# HW_ITC_LE.net
KiCad netlist of a schematic drawn in Altium Designer
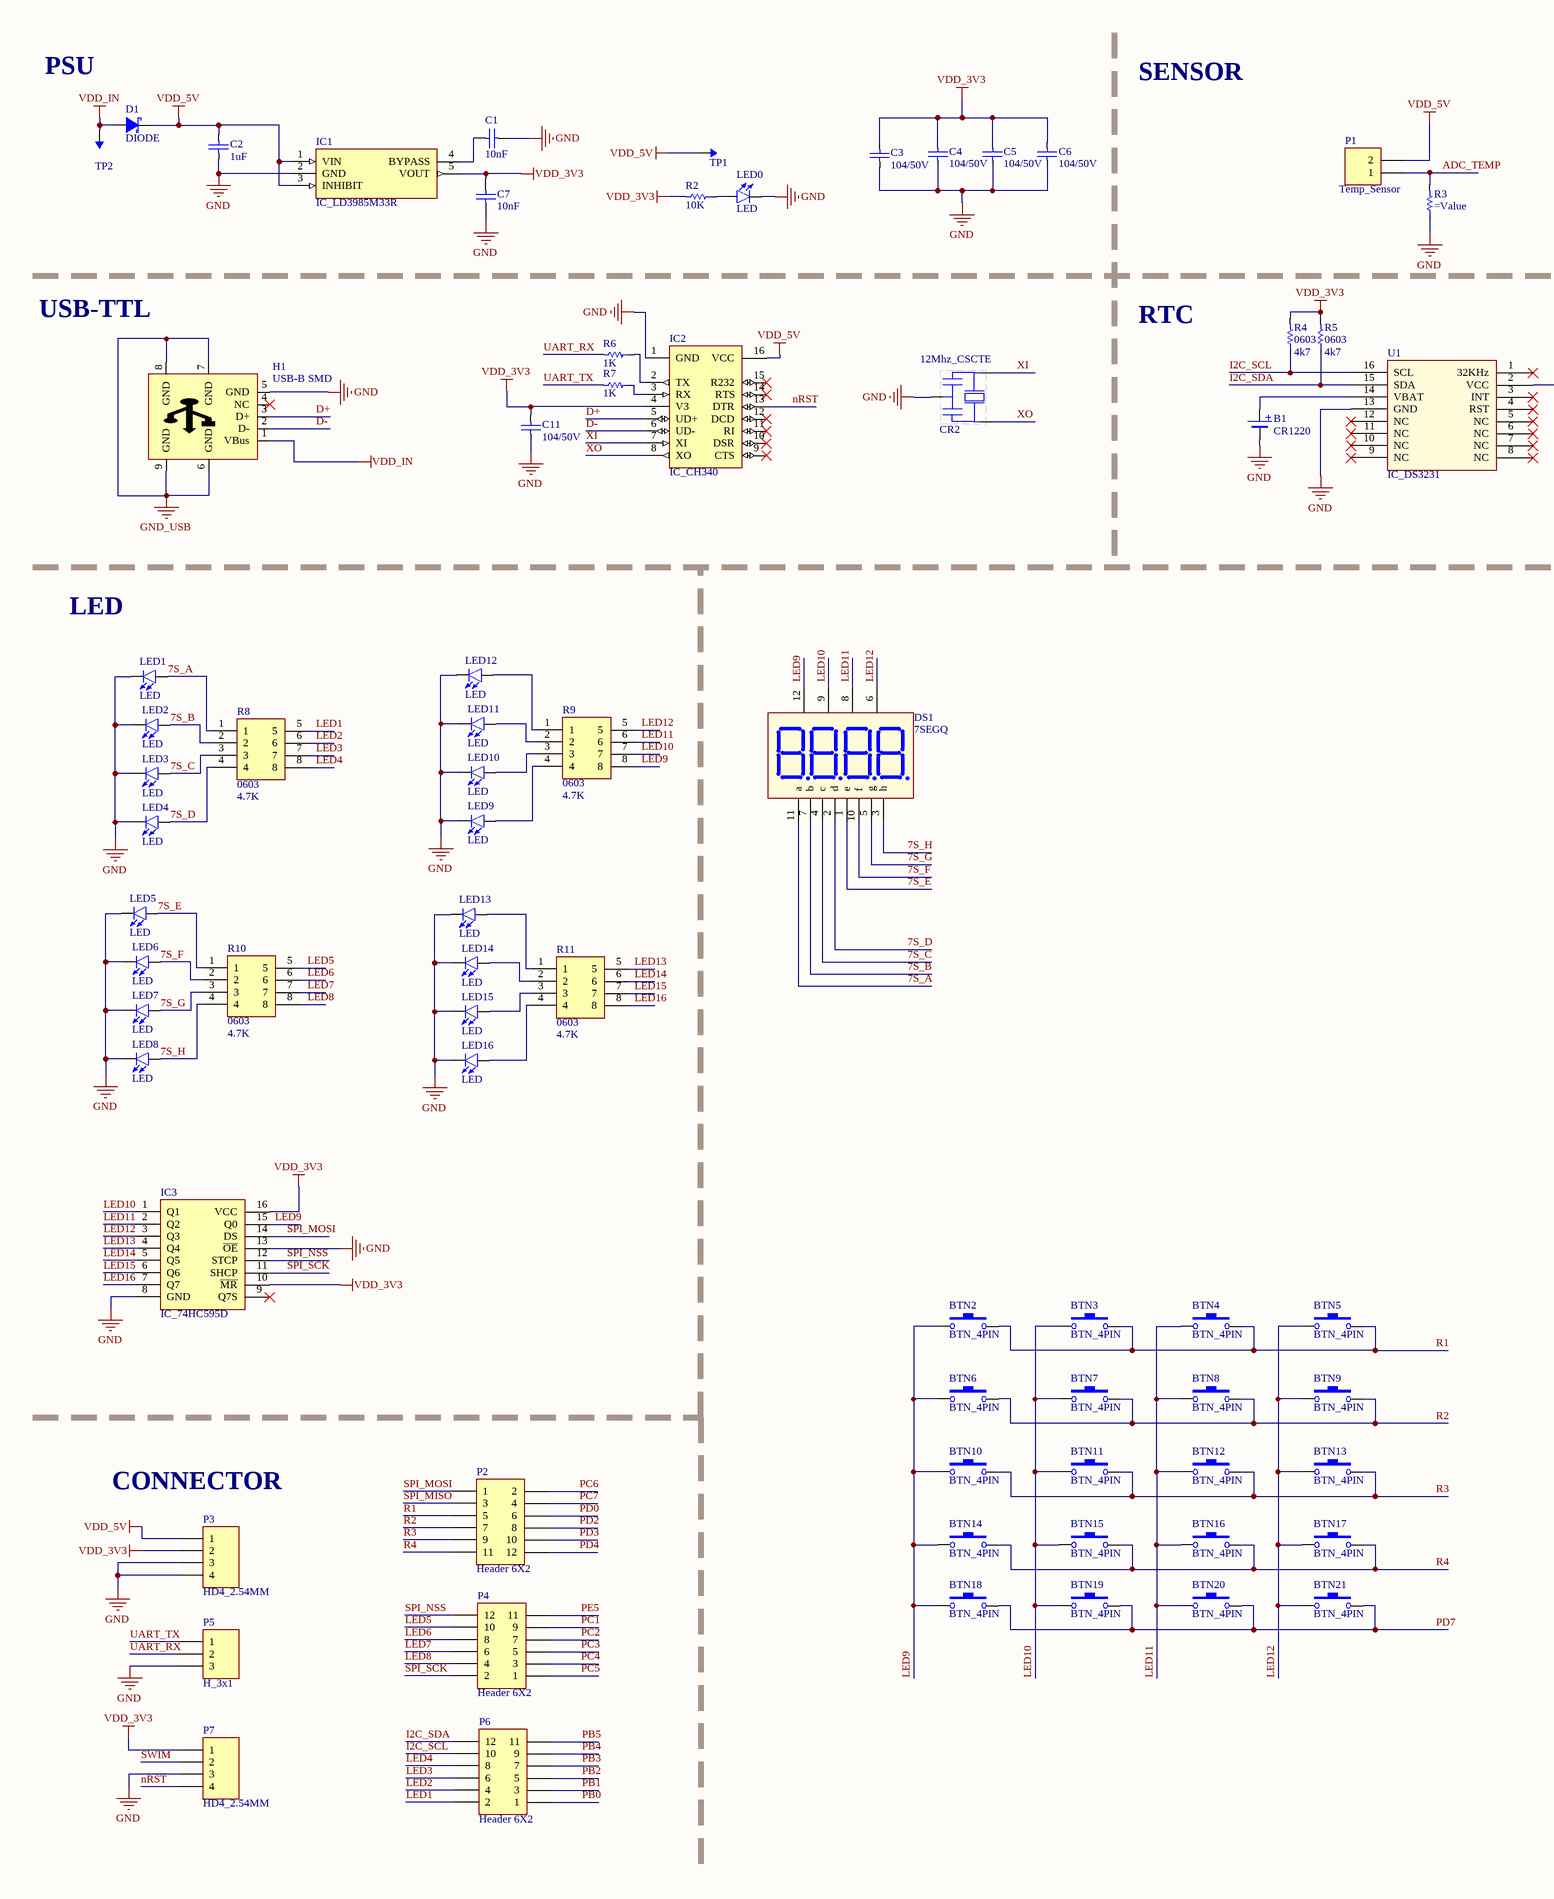
[diagram p0: HW_ITC_LE.SchDoc, left]
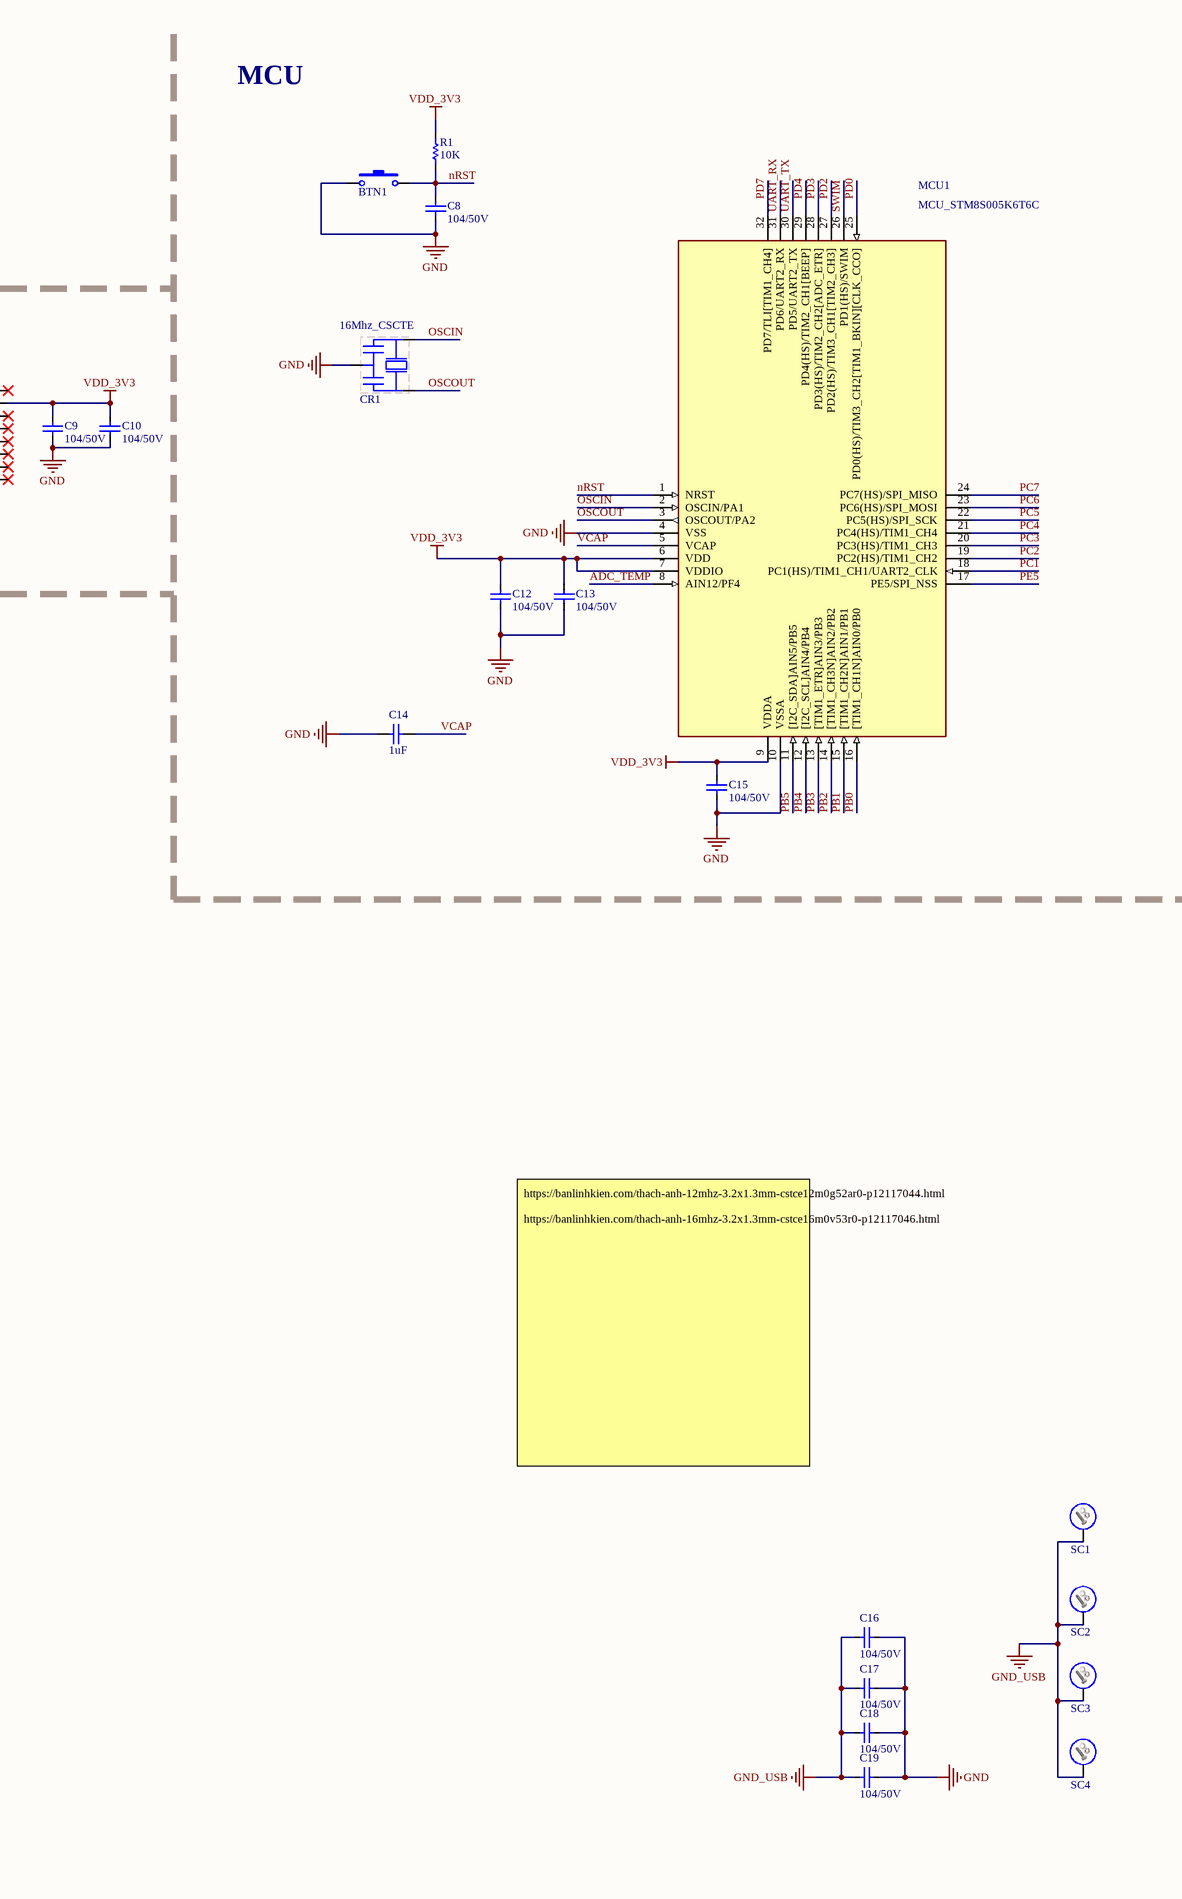
[diagram p1: HW_ITC_LE.SchDoc, right]

(export (version "E")
  (design (tool "Eeschema 10.0.6"))
  (components
    (comp (ref "B1")
      (value "CR1220")
      (footprint "CR1220")
      (libsource (lib "ITC_HHC") (part "Battery_CR1220"))
    )
    (comp (ref "BTN1")
      (value "EVQ-21307K")
      (footprint "BUTTON_2P_SMD")
      (description "PANASONIC   EVQ-21307K   SWITCH, TACTILE, SPST-NO, 20mA, 15VDC")
      (fields (field (name "MANUFACTURER") "Panasonic"))
      (libsource (lib "ITC_HHC") (part "BTN_2P_SMD"))
    )
    (comp (ref "BTN2")
      (value "BTN_4PIN")
      (footprint "BTN_4PIN - 6X6mm")
      (fields (field (name "PUBLISHER") "Altium Limited"))
      (libsource (lib "ITC_HHC") (part "BTN_4PIN"))
    )
    (comp (ref "BTN3")
      (value "BTN_4PIN")
      (footprint "BTN_4PIN - 6X6mm")
      (fields (field (name "PUBLISHER") "Altium Limited"))
      (libsource (lib "ITC_HHC") (part "BTN_4PIN"))
    )
    (comp (ref "BTN4")
      (value "BTN_4PIN")
      (footprint "BTN_4PIN - 6X6mm")
      (fields (field (name "PUBLISHER") "Altium Limited"))
      (libsource (lib "ITC_HHC") (part "BTN_4PIN"))
    )
    (comp (ref "BTN5")
      (value "BTN_4PIN")
      (footprint "BTN_4PIN - 6X6mm")
      (fields (field (name "PUBLISHER") "Altium Limited"))
      (libsource (lib "ITC_HHC") (part "BTN_4PIN"))
    )
    (comp (ref "BTN6")
      (value "BTN_4PIN")
      (footprint "BTN_4PIN - 6X6mm")
      (fields (field (name "PUBLISHER") "Altium Limited"))
      (libsource (lib "ITC_HHC") (part "BTN_4PIN"))
    )
    (comp (ref "BTN7")
      (value "BTN_4PIN")
      (footprint "BTN_4PIN - 6X6mm")
      (fields (field (name "PUBLISHER") "Altium Limited"))
      (libsource (lib "ITC_HHC") (part "BTN_4PIN"))
    )
    (comp (ref "BTN8")
      (value "BTN_4PIN")
      (footprint "BTN_4PIN - 6X6mm")
      (fields (field (name "PUBLISHER") "Altium Limited"))
      (libsource (lib "ITC_HHC") (part "BTN_4PIN"))
    )
    (comp (ref "BTN9")
      (value "BTN_4PIN")
      (footprint "BTN_4PIN - 6X6mm")
      (fields (field (name "PUBLISHER") "Altium Limited"))
      (libsource (lib "ITC_HHC") (part "BTN_4PIN"))
    )
    (comp (ref "BTN10")
      (value "BTN_4PIN")
      (footprint "BTN_4PIN - 6X6mm")
      (fields (field (name "PUBLISHER") "Altium Limited"))
      (libsource (lib "ITC_HHC") (part "BTN_4PIN"))
    )
    (comp (ref "BTN11")
      (value "BTN_4PIN")
      (footprint "BTN_4PIN - 6X6mm")
      (fields (field (name "PUBLISHER") "Altium Limited"))
      (libsource (lib "ITC_HHC") (part "BTN_4PIN"))
    )
    (comp (ref "BTN12")
      (value "BTN_4PIN")
      (footprint "BTN_4PIN - 6X6mm")
      (fields (field (name "PUBLISHER") "Altium Limited"))
      (libsource (lib "ITC_HHC") (part "BTN_4PIN"))
    )
    (comp (ref "BTN13")
      (value "BTN_4PIN")
      (footprint "BTN_4PIN - 6X6mm")
      (fields (field (name "PUBLISHER") "Altium Limited"))
      (libsource (lib "ITC_HHC") (part "BTN_4PIN"))
    )
    (comp (ref "BTN14")
      (value "BTN_4PIN")
      (footprint "BTN_4PIN - 6X6mm")
      (fields (field (name "PUBLISHER") "Altium Limited"))
      (libsource (lib "ITC_HHC") (part "BTN_4PIN"))
    )
    (comp (ref "BTN15")
      (value "BTN_4PIN")
      (footprint "BTN_4PIN - 6X6mm")
      (fields (field (name "PUBLISHER") "Altium Limited"))
      (libsource (lib "ITC_HHC") (part "BTN_4PIN"))
    )
    (comp (ref "BTN16")
      (value "BTN_4PIN")
      (footprint "BTN_4PIN - 6X6mm")
      (fields (field (name "PUBLISHER") "Altium Limited"))
      (libsource (lib "ITC_HHC") (part "BTN_4PIN"))
    )
    (comp (ref "BTN17")
      (value "BTN_4PIN")
      (footprint "BTN_4PIN - 6X6mm")
      (fields (field (name "PUBLISHER") "Altium Limited"))
      (libsource (lib "ITC_HHC") (part "BTN_4PIN"))
    )
    (comp (ref "BTN18")
      (value "BTN_4PIN")
      (footprint "BTN_4PIN - 6X6mm")
      (fields (field (name "PUBLISHER") "Altium Limited"))
      (libsource (lib "ITC_HHC") (part "BTN_4PIN"))
    )
    (comp (ref "BTN19")
      (value "BTN_4PIN")
      (footprint "BTN_4PIN - 6X6mm")
      (fields (field (name "PUBLISHER") "Altium Limited"))
      (libsource (lib "ITC_HHC") (part "BTN_4PIN"))
    )
    (comp (ref "BTN20")
      (value "BTN_4PIN")
      (footprint "BTN_4PIN - 6X6mm")
      (fields (field (name "PUBLISHER") "Altium Limited"))
      (libsource (lib "ITC_HHC") (part "BTN_4PIN"))
    )
    (comp (ref "BTN21")
      (value "BTN_4PIN")
      (footprint "BTN_4PIN - 6X6mm")
      (fields (field (name "PUBLISHER") "Altium Limited"))
      (libsource (lib "ITC_HHC") (part "BTN_4PIN"))
    )
    (comp (ref "C1")
      (value "10nF")
      (footprint "C0603")
      (description "Non-polarised capacitor")
      (libsource (lib "ITC_HHC") (part "Capacitor - non polarized"))
    )
    (comp (ref "C2")
      (value "1uF")
      (footprint "C0603")
      (description "CAP-CER-104-50V-0603-10%")
      (fields
        (field (name "MANUFACTURER") "Samsung")
        (field (name "MANUFACTURER PART NUMBER") "CL10B104KB8NNNC")
      )
      (libsource (lib "ITC_HHC") (part "C0603_104_50V"))
    )
    (comp (ref "C3")
      (value "104/50V")
      (footprint "C0603")
      (description "CAP-CER-104-50V-0603-10%")
      (fields
        (field (name "MANUFACTURER") "Samsung")
        (field (name "MANUFACTURER PART NUMBER") "CL10B104KB8NNNC")
      )
      (libsource (lib "ITC_HHC") (part "C0603_104_50V"))
    )
    (comp (ref "C4")
      (value "104/50V")
      (footprint "C0603")
      (description "CAP-CER-104-50V-0603-10%")
      (fields
        (field (name "MANUFACTURER") "Samsung")
        (field (name "MANUFACTURER PART NUMBER") "CL10B104KB8NNNC")
      )
      (libsource (lib "ITC_HHC") (part "C0603_104_50V"))
    )
    (comp (ref "C5")
      (value "104/50V")
      (footprint "C0603")
      (description "CAP-CER-104-50V-0603-10%")
      (fields
        (field (name "MANUFACTURER") "Samsung")
        (field (name "MANUFACTURER PART NUMBER") "CL10B104KB8NNNC")
      )
      (libsource (lib "ITC_HHC") (part "C0603_104_50V"))
    )
    (comp (ref "C6")
      (value "104/50V")
      (footprint "C0603")
      (description "CAP-CER-104-50V-0603-10%")
      (fields
        (field (name "MANUFACTURER") "Samsung")
        (field (name "MANUFACTURER PART NUMBER") "CL10B104KB8NNNC")
      )
      (libsource (lib "ITC_HHC") (part "C0603_104_50V"))
    )
    (comp (ref "C7")
      (value "10nF")
      (footprint "C0603")
      (description "Non-polarised capacitor")
      (libsource (lib "ITC_HHC") (part "Capacitor - non polarized"))
    )
    (comp (ref "C8")
      (value "104/50V")
      (footprint "C0603")
      (description "CAP-CER-104-50V-0603-10%")
      (fields
        (field (name "MANUFACTURER") "Samsung")
        (field (name "MANUFACTURER PART NUMBER") "CL10B104KB8NNNC")
      )
      (libsource (lib "ITC_HHC") (part "C0603_104_50V"))
    )
    (comp (ref "C9")
      (value "104/50V")
      (footprint "C0603")
      (description "CAP-CER-104-50V-0603-10%")
      (fields
        (field (name "MANUFACTURER") "Samsung")
        (field (name "MANUFACTURER PART NUMBER") "CL10B104KB8NNNC")
      )
      (libsource (lib "ITC_HHC") (part "C0603_104_50V"))
    )
    (comp (ref "C10")
      (value "104/50V")
      (footprint "C0603")
      (description "CAP-CER-104-50V-0603-10%")
      (fields
        (field (name "MANUFACTURER") "Samsung")
        (field (name "MANUFACTURER PART NUMBER") "CL10B104KB8NNNC")
      )
      (libsource (lib "ITC_HHC") (part "C0603_104_50V"))
    )
    (comp (ref "C11")
      (value "104/50V")
      (footprint "C0603")
      (description "CAP-CER-104-50V-0603-10%")
      (fields
        (field (name "MANUFACTURER") "Samsung")
        (field (name "MANUFACTURER PART NUMBER") "CL10B104KB8NNNC")
      )
      (libsource (lib "ITC_HHC") (part "C0603_104_50V"))
    )
    (comp (ref "C12")
      (value "104/50V")
      (footprint "C0603")
      (description "CAP-CER-104-50V-0603-10%")
      (fields
        (field (name "MANUFACTURER") "Samsung")
        (field (name "MANUFACTURER PART NUMBER") "CL10B104KB8NNNC")
      )
      (libsource (lib "ITC_HHC") (part "C0603_104_50V"))
    )
    (comp (ref "C13")
      (value "104/50V")
      (footprint "C0603")
      (description "CAP-CER-104-50V-0603-10%")
      (fields
        (field (name "MANUFACTURER") "Samsung")
        (field (name "MANUFACTURER PART NUMBER") "CL10B104KB8NNNC")
      )
      (libsource (lib "ITC_HHC") (part "C0603_104_50V"))
    )
    (comp (ref "C14")
      (value "1uF")
      (footprint "C0603")
      (description "Non-polarised capacitor")
      (libsource (lib "ITC_HHC") (part "Capacitor - non polarized"))
    )
    (comp (ref "C15")
      (value "104/50V")
      (footprint "C0603")
      (description "CAP-CER-104-50V-0603-10%")
      (fields
        (field (name "MANUFACTURER") "Samsung")
        (field (name "MANUFACTURER PART NUMBER") "CL10B104KB8NNNC")
      )
      (libsource (lib "ITC_HHC") (part "C0603_104_50V"))
    )
    (comp (ref "C16")
      (value "104/50V")
      (footprint "C0603")
      (description "CAP-CER-104-50V-0603-10%")
      (fields
        (field (name "MANUFACTURER") "Samsung")
        (field (name "MANUFACTURER PART NUMBER") "CL10B104KB8NNNC")
      )
      (libsource (lib "ITC_HHC") (part "C0603_104_50V"))
    )
    (comp (ref "C17")
      (value "104/50V")
      (footprint "C0603")
      (description "CAP-CER-104-50V-0603-10%")
      (fields
        (field (name "MANUFACTURER") "Samsung")
        (field (name "MANUFACTURER PART NUMBER") "CL10B104KB8NNNC")
      )
      (libsource (lib "ITC_HHC") (part "C0603_104_50V"))
    )
    (comp (ref "C18")
      (value "104/50V")
      (footprint "C0603")
      (description "CAP-CER-104-50V-0603-10%")
      (fields
        (field (name "MANUFACTURER") "Samsung")
        (field (name "MANUFACTURER PART NUMBER") "CL10B104KB8NNNC")
      )
      (libsource (lib "ITC_HHC") (part "C0603_104_50V"))
    )
    (comp (ref "C19")
      (value "104/50V")
      (footprint "C0603")
      (description "CAP-CER-104-50V-0603-10%")
      (fields
        (field (name "MANUFACTURER") "Samsung")
        (field (name "MANUFACTURER PART NUMBER") "CL10B104KB8NNNC")
      )
      (libsource (lib "ITC_HHC") (part "C0603_104_50V"))
    )
    (comp (ref "CR1")
      (value "16Mhz_CSCTE")
      (footprint "CRYSTAL_CSTCE_G_4520")
      (description "CER RES 6Mhz SMD")
      (libsource (lib "ITC_HHC") (part "CR_6Mhz_CSCTE"))
    )
    (comp (ref "CR2")
      (value "12Mhz_CSCTE")
      (footprint "CRYSTAL_CSTCE_G_4520")
      (description "CER RES 6Mhz SMD")
      (libsource (lib "ITC_HHC") (part "CR_6Mhz_CSCTE"))
    )
    (comp (ref "D1")
      (value "DIODE")
      (footprint "DIODE_SOD-123")
      (description "Schottky Diode RB060MM-60TFTR")
      (fields
        (field (name "MANUFACTURER_PART_NUMBER") "RB060MM-60TFTR")
        (field (name "MOUSER PART NUMBER") "755-RB060MM-60TFTR")
      )
      (libsource (lib "ITC_HHC") (part "DIODE_SOD-123FL"))
    )
    (comp (ref "DS1")
      (value "7SEGQ")
      (footprint "LED7SEG-4-0.36")
      (description "Four 7 Seg Dipslay")
      (libsource (lib "ITC_HHC") (part "LED7SEG-4"))
    )
    (comp (ref "H1")
      (value "USB-B SMD")
      (footprint "USB-B-Mini")
      (libsource (lib "ITC_HHC") (part "USB-B SMD"))
    )
    (comp (ref "IC1")
      (value "IC_LD3985M33R")
      (footprint "IC_LD3985M33R")
      (description "Integrated Circuit")
      (fields
        (field (name "MANUFACTURER_PART_NUMBER") "LD3985M33R")
        (field (name "MOUSER PART NUMBER") "511-LD3985M33R")
      )
      (libsource (lib "ITC_HHC") (part "IC_LD3985M33R"))
    )
    (comp (ref "IC2")
      (value "IC_CH340")
      (footprint "IC_CH340")
      (description "Circuit Breaker Magnetic 3Pole 40A 240VAC")
      (fields (field (name "MF") "Eaton") (field (name "MP") "CH340"))
      (libsource (lib "ITC_HHC") (part "IC_CH340"))
    )
    (comp (ref "IC3")
      (value "IC_74HC595D")
      (footprint "IC_74HC595")
      (description "Integrated Circuit")
      (fields (field (name "MANUFACTURER_PART_NUMBER") "74HC595D"))
      (libsource (lib "ITC_HHC") (part "IC_74HC595D"))
    )
    (comp (ref "LED0")
      (value "LED")
      (footprint "LED_0805_BLUE")
      (libsource (lib "ITC_HHC") (part "LED_0805"))
    )
    (comp (ref "LED1")
      (value "LED")
      (footprint "LED_0805_BLUE")
      (libsource (lib "ITC_HHC") (part "LED_0805"))
    )
    (comp (ref "LED2")
      (value "LED")
      (footprint "LED_0805_BLUE")
      (libsource (lib "ITC_HHC") (part "LED_0805"))
    )
    (comp (ref "LED3")
      (value "LED")
      (footprint "LED_0805_BLUE")
      (libsource (lib "ITC_HHC") (part "LED_0805"))
    )
    (comp (ref "LED4")
      (value "LED")
      (footprint "LED_0805_BLUE")
      (libsource (lib "ITC_HHC") (part "LED_0805"))
    )
    (comp (ref "LED5")
      (value "LED")
      (footprint "LED_0805_BLUE")
      (libsource (lib "ITC_HHC") (part "LED_0805"))
    )
    (comp (ref "LED6")
      (value "LED")
      (footprint "LED_0805_BLUE")
      (libsource (lib "ITC_HHC") (part "LED_0805"))
    )
    (comp (ref "LED7")
      (value "LED")
      (footprint "LED_0805_BLUE")
      (libsource (lib "ITC_HHC") (part "LED_0805"))
    )
    (comp (ref "LED8")
      (value "LED")
      (footprint "LED_0805_BLUE")
      (libsource (lib "ITC_HHC") (part "LED_0805"))
    )
    (comp (ref "LED9")
      (value "LED")
      (footprint "LED_0805_BLUE")
      (libsource (lib "ITC_HHC") (part "LED_0805"))
    )
    (comp (ref "LED10")
      (value "LED")
      (footprint "LED_0805_BLUE")
      (libsource (lib "ITC_HHC") (part "LED_0805"))
    )
    (comp (ref "LED11")
      (value "LED")
      (footprint "LED_0805_BLUE")
      (libsource (lib "ITC_HHC") (part "LED_0805"))
    )
    (comp (ref "LED12")
      (value "LED")
      (footprint "LED_0805_BLUE")
      (libsource (lib "ITC_HHC") (part "LED_0805"))
    )
    (comp (ref "LED13")
      (value "LED")
      (footprint "LED_0805_BLUE")
      (libsource (lib "ITC_HHC") (part "LED_0805"))
    )
    (comp (ref "LED14")
      (value "LED")
      (footprint "LED_0805_BLUE")
      (libsource (lib "ITC_HHC") (part "LED_0805"))
    )
    (comp (ref "LED15")
      (value "LED")
      (footprint "LED_0805_BLUE")
      (libsource (lib "ITC_HHC") (part "LED_0805"))
    )
    (comp (ref "LED16")
      (value "LED")
      (footprint "LED_0805_BLUE")
      (libsource (lib "ITC_HHC") (part "LED_0805"))
    )
    (comp (ref "MCU1")
      (value "MCU_STM8S005K6T6C")
      (footprint "MCU_STM8S005K6T6C")
      (description "Integrated Circuit")
      (fields
        (field (name "MANUFACTURER_PART_NUMBER") "STM8S005K6T6C")
        (field (name "MOUSER PART NUMBER") "511-STM8S005K6T6C")
      )
      (libsource (lib "ITC_HHC") (part "MCU_STM8S005K6T6C"))
    )
    (comp (ref "P1")
      (value "Temp_Sensor")
      (footprint "H_2x1")
      (description "HEADER_2POS 2.54MM")
      (fields
        (field (name "MANUFACTURER") "AMP - TE CONNECTIVITY")
        (field (name "MANUFACTURER PART NUMBER") "640456-2")
      )
      (libsource (lib "ITC_HHC") (part "HD2_WHITE_2.54MM"))
    )
    (comp (ref "P2")
      (value "Header 6X2")
      (footprint "HDR2X6")
      (fields (field (name "PUBLISHER") "Altium Limited"))
      (libsource (lib "") (part "Header 6X2_1"))
    )
    (comp (ref "P3")
      (value "HD4_2.54MM")
      (footprint "HDR_2x2")
      (description "HEADER_4POS 2.54MM")
      (fields
        (field (name "MANUFACTURER") "AMP - TE CONNECTIVITY")
        (field (name "MANUFACTURER PART NUMBER") "640456-4")
      )
      (libsource (lib "ITC_HHC") (part "HD4_2.54MM"))
    )
    (comp (ref "P4")
      (value "Header 6X2")
      (footprint "HDR2X6")
      (fields (field (name "PUBLISHER") "Altium Limited"))
      (libsource (lib "ITC_HHC") (part "Header 6X2"))
    )
    (comp (ref "P5")
      (value "H_3x1")
      (footprint "HDR1X3")
      (description "Header, 3-Pin")
      (fields (field (name "PUBLISHER") "Altium Limited"))
      (libsource (lib "ITC_HHC") (part "J_3x1"))
    )
    (comp (ref "P6")
      (value "Header 6X2")
      (footprint "HDR2X6")
      (fields (field (name "PUBLISHER") "Altium Limited"))
      (libsource (lib "ITC_HHC") (part "Header 6X2"))
    )
    (comp (ref "P7")
      (value "HD4_2.54MM")
      (footprint "HDR4")
      (description "HEADER_4POS 2.54MM")
      (fields
        (field (name "MANUFACTURER") "AMP - TE CONNECTIVITY")
        (field (name "MANUFACTURER PART NUMBER") "640456-4")
      )
      (libsource (lib "ITC_HHC") (part "HD4_2.54MM"))
    )
    (comp (ref "R1")
      (value "10K")
      (footprint "R0603")
      (description "RES SMD 10K OHM 0.5% 1/16W 0603")
      (fields
        (field (name "MANUFACTURER") "Susumu")
        (field (name "MANUFACTURER PART NUMBER") "RR0816P-103-D")
      )
      (libsource (lib "ITC_HHC") (part "R0603_103_1/16W"))
    )
    (comp (ref "R2")
      (value "10K")
      (footprint "R0603")
      (description "RES SMD 10K OHM 0.5% 1/16W 0603")
      (fields
        (field (name "MANUFACTURER") "Susumu")
        (field (name "MANUFACTURER PART NUMBER") "RR0816P-103-D")
      )
      (libsource (lib "ITC_HHC") (part "R0603_103_1/16W"))
    )
    (comp (ref "R3")
      (value "~")
      (footprint "R0603")
      (description "Resistor - 5%")
      (libsource (lib "ITC_HHC") (part "Resistor - 5%"))
    )
    (comp (ref "R4")
      (value "R0603_4.7K_100mW_5%")
      (footprint "R0603")
      (description "RES SMD 4.7k OHM 5% 100mW")
      (fields
        (field (name "MANUFACTURER") "Yageo")
        (field (name "MANUFACTURER PART NUMBER") "RC0603JR-074K7L")
        (field (name "CASE CODE - IN") "0603")
        (field (name "RESISTANCE") "4k7")
      )
      (libsource (lib "ITC_HHC") (part "R0603_4.7K_100mW_5%"))
    )
    (comp (ref "R5")
      (value "R0603_4.7K_100mW_5%")
      (footprint "R0603")
      (description "RES SMD 4.7k OHM 5% 100mW")
      (fields
        (field (name "MANUFACTURER") "Yageo")
        (field (name "MANUFACTURER PART NUMBER") "RC0603JR-074K7L")
        (field (name "CASE CODE - IN") "0603")
        (field (name "RESISTANCE") "4k7")
      )
      (libsource (lib "ITC_HHC") (part "R0603_4.7K_100mW_5%"))
    )
    (comp (ref "R6")
      (value "1K")
      (footprint "R0603")
      (description "Resistor - 5%")
      (libsource (lib "ITC_HHC") (part "Resistor - 5%"))
    )
    (comp (ref "R7")
      (value "1K")
      (footprint "R0603")
      (description "Resistor - 5%")
      (libsource (lib "ITC_HHC") (part "Resistor - 5%"))
    )
    (comp (ref "R8")
      (value "R0603_4.7Kohm_4xArray")
      (footprint "R0603_4xArray")
      (description "RES ARRAY 2 RES 4.7K OHM 0603")
      (fields
        (field (name "MANUFACTURER") "CTS")
        (field (name "MANUFACTURER PART NUMBER") "742C043220JP")
        (field (name "CASE/PACKAGE") "0603")
        (field (name "RESISTANCE") "4.7K")
      )
      (libsource (lib "ITC_HHC") (part "R0603_4.7Kohm_4xArray"))
    )
    (comp (ref "R9")
      (value "R0603_4.7Kohm_4xArray")
      (footprint "R0603_4xArray")
      (description "RES ARRAY 2 RES 4.7K OHM 0603")
      (fields
        (field (name "MANUFACTURER") "CTS")
        (field (name "MANUFACTURER PART NUMBER") "742C043220JP")
        (field (name "CASE/PACKAGE") "0603")
        (field (name "RESISTANCE") "4.7K")
      )
      (libsource (lib "ITC_HHC") (part "R0603_4.7Kohm_4xArray"))
    )
    (comp (ref "R10")
      (value "R0603_4.7Kohm_4xArray")
      (footprint "R0603_4xArray")
      (description "RES ARRAY 2 RES 4.7K OHM 0603")
      (fields
        (field (name "MANUFACTURER") "CTS")
        (field (name "MANUFACTURER PART NUMBER") "742C043220JP")
        (field (name "CASE/PACKAGE") "0603")
        (field (name "RESISTANCE") "4.7K")
      )
      (libsource (lib "ITC_HHC") (part "R0603_4.7Kohm_4xArray"))
    )
    (comp (ref "R11")
      (value "R0603_4.7Kohm_4xArray")
      (footprint "R0603_4xArray")
      (description "RES ARRAY 2 RES 4.7K OHM 0603")
      (fields
        (field (name "MANUFACTURER") "CTS")
        (field (name "MANUFACTURER PART NUMBER") "742C043220JP")
        (field (name "CASE/PACKAGE") "0603")
        (field (name "RESISTANCE") "4.7K")
      )
      (libsource (lib "ITC_HHC") (part "R0603_4.7Kohm_4xArray"))
    )
    (comp (ref "SC1")
      (value "SCREW")
      (footprint "PAD_SCREW_3.2MM")
      (libsource (lib "ITC_HHC") (part "SCREW"))
    )
    (comp (ref "SC2")
      (value "SCREW")
      (footprint "PAD_SCREW_3.2MM")
      (libsource (lib "ITC_HHC") (part "SCREW"))
    )
    (comp (ref "SC3")
      (value "SCREW")
      (footprint "PAD_SCREW_3.2MM")
      (libsource (lib "ITC_HHC") (part "SCREW"))
    )
    (comp (ref "SC4")
      (value "SCREW")
      (footprint "PAD_SCREW_3.2MM")
      (libsource (lib "ITC_HHC") (part "SCREW"))
    )
    (comp (ref "TP1") (value "TESTPOINT") (footprint "TP-R40") (libsource (lib "ITC_HHC") (part "TESTPOINT")))
    (comp (ref "TP2") (value "TESTPOINT") (footprint "TP-R40") (libsource (lib "ITC_HHC") (part "TESTPOINT")))
    (comp (ref "U1")
      (value "IC_DS3231")
      (footprint "DS3231")
      (description "IC RTC CLK/CALENDAR I2C 16-SOIC")
      (libsource (lib "ITC_HHC") (part "IC_DS3231"))
    )
  )
  (nets
    (net (code "1") (name "/7S_A") (class "Default")
      (node (ref "DS1") (pin "11") (pinfunction "a_11") (pintype "passive"))
      (node (ref "LED1") (pin "A") (pinfunction "A_A") (pintype "passive"))
      (node (ref "R8") (pin "1") (pinfunction "1_1") (pintype "passive"))
    )
    (net (code "2") (name "/7S_B") (class "Default")
      (node (ref "DS1") (pin "7") (pinfunction "b_7") (pintype "passive"))
      (node (ref "LED2") (pin "A") (pinfunction "A_A") (pintype "passive"))
      (node (ref "R8") (pin "2") (pinfunction "2_2") (pintype "passive"))
    )
    (net (code "3") (name "/7S_C") (class "Default")
      (node (ref "DS1") (pin "4") (pinfunction "c_4") (pintype "passive"))
      (node (ref "LED3") (pin "A") (pinfunction "A_A") (pintype "passive"))
      (node (ref "R8") (pin "3") (pinfunction "3_3") (pintype "passive"))
    )
    (net (code "4") (name "/7S_D") (class "Default")
      (node (ref "DS1") (pin "2") (pinfunction "d_2") (pintype "passive"))
      (node (ref "LED4") (pin "A") (pinfunction "A_A") (pintype "passive"))
      (node (ref "R8") (pin "4") (pinfunction "4_4") (pintype "passive"))
    )
    (net (code "5") (name "/7S_E") (class "Default")
      (node (ref "DS1") (pin "1") (pinfunction "e_1") (pintype "passive"))
      (node (ref "LED5") (pin "A") (pinfunction "A_A") (pintype "passive"))
      (node (ref "R10") (pin "1") (pinfunction "1_1") (pintype "passive"))
    )
    (net (code "6") (name "/7S_F") (class "Default")
      (node (ref "DS1") (pin "10") (pinfunction "f_10") (pintype "passive"))
      (node (ref "LED6") (pin "A") (pinfunction "A_A") (pintype "passive"))
      (node (ref "R10") (pin "2") (pinfunction "2_2") (pintype "passive"))
    )
    (net (code "7") (name "/7S_G") (class "Default")
      (node (ref "DS1") (pin "5") (pinfunction "g_5") (pintype "passive"))
      (node (ref "LED7") (pin "A") (pinfunction "A_A") (pintype "passive"))
      (node (ref "R10") (pin "3") (pinfunction "3_3") (pintype "passive"))
    )
    (net (code "8") (name "/7S_H") (class "Default")
      (node (ref "DS1") (pin "3") (pinfunction "h_3") (pintype "passive"))
      (node (ref "LED8") (pin "A") (pinfunction "A_A") (pintype "passive"))
      (node (ref "R10") (pin "4") (pinfunction "4_4") (pintype "passive"))
    )
    (net (code "9") (name "/ADC_TEMP") (class "Default")
      (node (ref "MCU1") (pin "8") (pinfunction "AIN12/PF4_8") (pintype "input"))
      (node (ref "P1") (pin "1") (pinfunction "1_1") (pintype "passive"))
      (node (ref "R3") (pin "2") (pinfunction "2_2") (pintype "passive"))
    )
    (net (code "10") (name "/D+") (class "Default")
      (node (ref "H1") (pin "3") (pinfunction "D+_3") (pintype "passive"))
      (node (ref "IC2") (pin "5") (pinfunction "UD+_5") (pintype "bidirectional"))
    )
    (net (code "11") (name "/D-") (class "Default")
      (node (ref "H1") (pin "2") (pinfunction "D-_2") (pintype "passive"))
      (node (ref "IC2") (pin "6") (pinfunction "UD-_6") (pintype "bidirectional"))
    )
    (net (code "12") (name "/I2C_SCL") (class "Default")
      (node (ref "P6") (pin "10") (pinfunction "10_10") (pintype "passive"))
      (node (ref "R4") (pin "1") (pinfunction "1_1") (pintype "passive"))
      (node (ref "U1") (pin "16") (pinfunction "SCL_16") (pintype "passive"))
    )
    (net (code "13") (name "/I2C_SDA") (class "Default")
      (node (ref "P6") (pin "12") (pinfunction "12_12") (pintype "passive"))
      (node (ref "R5") (pin "1") (pinfunction "1_1") (pintype "passive"))
      (node (ref "U1") (pin "15") (pinfunction "SDA_15") (pintype "passive"))
    )
    (net (code "14") (name "/LED1") (class "Default")
      (node (ref "P6") (pin "2") (pinfunction "2_2") (pintype "passive"))
      (node (ref "R8") (pin "5") (pinfunction "5_5") (pintype "passive"))
    )
    (net (code "15") (name "/LED2") (class "Default")
      (node (ref "P6") (pin "4") (pinfunction "4_4") (pintype "passive"))
      (node (ref "R8") (pin "6") (pinfunction "6_6") (pintype "passive"))
    )
    (net (code "16") (name "/LED3") (class "Default")
      (node (ref "P6") (pin "6") (pinfunction "6_6") (pintype "passive"))
      (node (ref "R8") (pin "7") (pinfunction "7_7") (pintype "passive"))
    )
    (net (code "17") (name "/LED4") (class "Default")
      (node (ref "P6") (pin "8") (pinfunction "8_8") (pintype "passive"))
      (node (ref "R8") (pin "8") (pinfunction "8_8") (pintype "passive"))
    )
    (net (code "18") (name "/LED5") (class "Default")
      (node (ref "P4") (pin "10") (pinfunction "10_10") (pintype "passive"))
      (node (ref "R10") (pin "5") (pinfunction "5_5") (pintype "passive"))
    )
    (net (code "19") (name "/LED6") (class "Default")
      (node (ref "P4") (pin "8") (pinfunction "8_8") (pintype "passive"))
      (node (ref "R10") (pin "6") (pinfunction "6_6") (pintype "passive"))
    )
    (net (code "20") (name "/LED7") (class "Default")
      (node (ref "P4") (pin "6") (pinfunction "6_6") (pintype "passive"))
      (node (ref "R10") (pin "7") (pinfunction "7_7") (pintype "passive"))
    )
    (net (code "21") (name "/LED8") (class "Default")
      (node (ref "P4") (pin "4") (pinfunction "4_4") (pintype "passive"))
      (node (ref "R10") (pin "8") (pinfunction "8_8") (pintype "passive"))
    )
    (net (code "22") (name "/LED9") (class "Default")
      (node (ref "BTN10") (pin "1") (pinfunction "1_1") (pintype "passive"))
      (node (ref "BTN14") (pin "1") (pinfunction "1_1") (pintype "passive"))
      (node (ref "BTN18") (pin "1") (pinfunction "1_1") (pintype "passive"))
      (node (ref "BTN2") (pin "1") (pinfunction "1_1") (pintype "passive"))
      (node (ref "BTN6") (pin "1") (pinfunction "1_1") (pintype "passive"))
      (node (ref "DS1") (pin "12") (pinfunction "V1_12") (pintype "passive"))
      (node (ref "IC3") (pin "15") (pinfunction "Q0_15") (pintype "passive"))
      (node (ref "R9") (pin "8") (pinfunction "8_8") (pintype "passive"))
    )
    (net (code "23") (name "/LED10") (class "Default")
      (node (ref "BTN11") (pin "1") (pinfunction "1_1") (pintype "passive"))
      (node (ref "BTN15") (pin "1") (pinfunction "1_1") (pintype "passive"))
      (node (ref "BTN19") (pin "1") (pinfunction "1_1") (pintype "passive"))
      (node (ref "BTN3") (pin "1") (pinfunction "1_1") (pintype "passive"))
      (node (ref "BTN7") (pin "1") (pinfunction "1_1") (pintype "passive"))
      (node (ref "DS1") (pin "9") (pinfunction "V2_9") (pintype "passive"))
      (node (ref "IC3") (pin "1") (pinfunction "Q1_1") (pintype "passive"))
      (node (ref "R9") (pin "7") (pinfunction "7_7") (pintype "passive"))
    )
    (net (code "24") (name "/LED11") (class "Default")
      (node (ref "BTN12") (pin "1") (pinfunction "1_1") (pintype "passive"))
      (node (ref "BTN16") (pin "1") (pinfunction "1_1") (pintype "passive"))
      (node (ref "BTN20") (pin "1") (pinfunction "1_1") (pintype "passive"))
      (node (ref "BTN4") (pin "1") (pinfunction "1_1") (pintype "passive"))
      (node (ref "BTN8") (pin "1") (pinfunction "1_1") (pintype "passive"))
      (node (ref "DS1") (pin "8") (pinfunction "V3_8") (pintype "passive"))
      (node (ref "IC3") (pin "2") (pinfunction "Q2_2") (pintype "passive"))
      (node (ref "R9") (pin "6") (pinfunction "6_6") (pintype "passive"))
    )
    (net (code "25") (name "/LED12") (class "Default")
      (node (ref "BTN13") (pin "1") (pinfunction "1_1") (pintype "passive"))
      (node (ref "BTN17") (pin "1") (pinfunction "1_1") (pintype "passive"))
      (node (ref "BTN21") (pin "1") (pinfunction "1_1") (pintype "passive"))
      (node (ref "BTN5") (pin "1") (pinfunction "1_1") (pintype "passive"))
      (node (ref "BTN9") (pin "1") (pinfunction "1_1") (pintype "passive"))
      (node (ref "DS1") (pin "6") (pinfunction "V4_6") (pintype "passive"))
      (node (ref "IC3") (pin "3") (pinfunction "Q3_3") (pintype "passive"))
      (node (ref "R9") (pin "5") (pinfunction "5_5") (pintype "passive"))
    )
    (net (code "26") (name "/LED13") (class "Default")
      (node (ref "IC3") (pin "4") (pinfunction "Q4_4") (pintype "passive"))
      (node (ref "R11") (pin "5") (pinfunction "5_5") (pintype "passive"))
    )
    (net (code "27") (name "/LED14") (class "Default")
      (node (ref "IC3") (pin "5") (pinfunction "Q5_5") (pintype "passive"))
      (node (ref "R11") (pin "6") (pinfunction "6_6") (pintype "passive"))
    )
    (net (code "28") (name "/LED15") (class "Default")
      (node (ref "IC3") (pin "6") (pinfunction "Q6_6") (pintype "passive"))
      (node (ref "R11") (pin "7") (pinfunction "7_7") (pintype "passive"))
    )
    (net (code "29") (name "/LED16") (class "Default")
      (node (ref "IC3") (pin "7") (pinfunction "Q7_7") (pintype "passive"))
      (node (ref "R11") (pin "8") (pinfunction "8_8") (pintype "passive"))
    )
    (net (code "30") (name "/OSCIN") (class "Default")
      (node (ref "CR1") (pin "1") (pinfunction "1_1") (pintype "passive"))
      (node (ref "MCU1") (pin "2") (pinfunction "OSCIN/PA1_2") (pintype "input"))
    )
    (net (code "31") (name "/OSCOUT") (class "Default")
      (node (ref "CR1") (pin "3") (pinfunction "3_3") (pintype "passive"))
      (node (ref "MCU1") (pin "3") (pinfunction "OSCOUT/PA2_3") (pintype "output"))
    )
    (net (code "32") (name "/PB0") (class "Default")
      (node (ref "MCU1") (pin "16") (pinfunction "[TIM1_CH1N]AIN0/PB0_16") (pintype "input"))
      (node (ref "P6") (pin "1") (pinfunction "1_1") (pintype "passive"))
    )
    (net (code "33") (name "/PB1") (class "Default")
      (node (ref "MCU1") (pin "15") (pinfunction "[TIM1_CH2N]AIN1/PB1_15") (pintype "input"))
      (node (ref "P6") (pin "3") (pinfunction "3_3") (pintype "passive"))
    )
    (net (code "34") (name "/PB2") (class "Default")
      (node (ref "MCU1") (pin "14") (pinfunction "[TIM1_CH3N]AIN2/PB2_14") (pintype "input"))
      (node (ref "P6") (pin "5") (pinfunction "5_5") (pintype "passive"))
    )
    (net (code "35") (name "/PB3") (class "Default")
      (node (ref "MCU1") (pin "13") (pinfunction "[TIM1_ETR]AIN3/PB3_13") (pintype "input"))
      (node (ref "P6") (pin "7") (pinfunction "7_7") (pintype "passive"))
    )
    (net (code "36") (name "/PB4") (class "Default")
      (node (ref "MCU1") (pin "12") (pinfunction "[I2C_SCL]AIN4/PB4_12") (pintype "input"))
      (node (ref "P6") (pin "9") (pinfunction "9_9") (pintype "passive"))
    )
    (net (code "37") (name "/PB5") (class "Default")
      (node (ref "MCU1") (pin "11") (pinfunction "[I2C_SDA]AIN5/PB5_11") (pintype "input"))
      (node (ref "P6") (pin "11") (pinfunction "11_11") (pintype "passive"))
    )
    (net (code "38") (name "/PC1") (class "Default")
      (node (ref "MCU1") (pin "18") (pinfunction "PC1(HS)/TIM1_CH1/UART2_CLK_18") (pintype "input"))
      (node (ref "P4") (pin "9") (pinfunction "9_9") (pintype "passive"))
    )
    (net (code "39") (name "/PC2") (class "Default")
      (node (ref "MCU1") (pin "19") (pinfunction "PC2(HS)/TIM1_CH2_19") (pintype "passive"))
      (node (ref "P4") (pin "7") (pinfunction "7_7") (pintype "passive"))
    )
    (net (code "40") (name "/PC3") (class "Default")
      (node (ref "MCU1") (pin "20") (pinfunction "PC3(HS)/TIM1_CH3_20") (pintype "passive"))
      (node (ref "P4") (pin "5") (pinfunction "5_5") (pintype "passive"))
    )
    (net (code "41") (name "/PC4") (class "Default")
      (node (ref "MCU1") (pin "21") (pinfunction "PC4(HS)/TIM1_CH4_21") (pintype "passive"))
      (node (ref "P4") (pin "3") (pinfunction "3_3") (pintype "passive"))
    )
    (net (code "42") (name "/PC5") (class "Default")
      (node (ref "MCU1") (pin "22") (pinfunction "PC5(HS)/SPI_SCK_22") (pintype "passive"))
      (node (ref "P4") (pin "1") (pinfunction "1_1") (pintype "passive"))
    )
    (net (code "43") (name "/PC6") (class "Default")
      (node (ref "MCU1") (pin "23") (pinfunction "PC6(HS)/SPI_MOSI_23") (pintype "passive"))
      (node (ref "P2") (pin "2") (pinfunction "2_2") (pintype "passive"))
    )
    (net (code "44") (name "/PC7") (class "Default")
      (node (ref "MCU1") (pin "24") (pinfunction "PC7(HS)/SPI_MISO_24") (pintype "passive"))
      (node (ref "P2") (pin "4") (pinfunction "4_4") (pintype "passive"))
    )
    (net (code "45") (name "/PD0") (class "Default")
      (node (ref "MCU1") (pin "25") (pinfunction "PD0(HS)/TIM3_CH2[TIM1_BKIN][CLK_CCO]_25") (pintype "input"))
      (node (ref "P2") (pin "6") (pinfunction "6_6") (pintype "passive"))
    )
    (net (code "46") (name "/PD2") (class "Default")
      (node (ref "MCU1") (pin "27") (pinfunction "PD2(HS)/TIM3_CH1[TIM2_CH3]_27") (pintype "passive"))
      (node (ref "P2") (pin "8") (pinfunction "8_8") (pintype "passive"))
    )
    (net (code "47") (name "/PD3") (class "Default")
      (node (ref "MCU1") (pin "28") (pinfunction "PD3(HS)/TIM2_CH2[ADC_ETR]_28") (pintype "passive"))
      (node (ref "P2") (pin "10") (pinfunction "10_10") (pintype "passive"))
    )
    (net (code "48") (name "/PD4") (class "Default")
      (node (ref "MCU1") (pin "29") (pinfunction "PD4(HS)/TIM2_CH1[BEEP]_29") (pintype "passive"))
      (node (ref "P2") (pin "12") (pinfunction "12_12") (pintype "passive"))
    )
    (net (code "49") (name "/PD7") (class "Default")
      (node (ref "BTN18") (pin "2") (pinfunction "2_2") (pintype "passive"))
      (node (ref "BTN19") (pin "2") (pinfunction "2_2") (pintype "passive"))
      (node (ref "BTN20") (pin "2") (pinfunction "2_2") (pintype "passive"))
      (node (ref "BTN21") (pin "2") (pinfunction "2_2") (pintype "passive"))
      (node (ref "MCU1") (pin "32") (pinfunction "PD7/TLI[TIM1_CH4]_32") (pintype "passive"))
    )
    (net (code "50") (name "/PE5") (class "Default")
      (node (ref "MCU1") (pin "17") (pinfunction "PE5/SPI_NSS_17") (pintype "passive"))
      (node (ref "P4") (pin "11") (pinfunction "11_11") (pintype "passive"))
    )
    (net (code "51") (name "/R1") (class "Default")
      (node (ref "BTN2") (pin "2") (pinfunction "2_2") (pintype "passive"))
      (node (ref "BTN3") (pin "2") (pinfunction "2_2") (pintype "passive"))
      (node (ref "BTN4") (pin "2") (pinfunction "2_2") (pintype "passive"))
      (node (ref "BTN5") (pin "2") (pinfunction "2_2") (pintype "passive"))
      (node (ref "P2") (pin "5") (pinfunction "5_5") (pintype "passive"))
    )
    (net (code "52") (name "/R2") (class "Default")
      (node (ref "BTN6") (pin "2") (pinfunction "2_2") (pintype "passive"))
      (node (ref "BTN7") (pin "2") (pinfunction "2_2") (pintype "passive"))
      (node (ref "BTN8") (pin "2") (pinfunction "2_2") (pintype "passive"))
      (node (ref "BTN9") (pin "2") (pinfunction "2_2") (pintype "passive"))
      (node (ref "P2") (pin "7") (pinfunction "7_7") (pintype "passive"))
    )
    (net (code "53") (name "/R3") (class "Default")
      (node (ref "BTN10") (pin "2") (pinfunction "2_2") (pintype "passive"))
      (node (ref "BTN11") (pin "2") (pinfunction "2_2") (pintype "passive"))
      (node (ref "BTN12") (pin "2") (pinfunction "2_2") (pintype "passive"))
      (node (ref "BTN13") (pin "2") (pinfunction "2_2") (pintype "passive"))
      (node (ref "P2") (pin "9") (pinfunction "9_9") (pintype "passive"))
    )
    (net (code "54") (name "/R4") (class "Default")
      (node (ref "BTN14") (pin "2") (pinfunction "2_2") (pintype "passive"))
      (node (ref "BTN15") (pin "2") (pinfunction "2_2") (pintype "passive"))
      (node (ref "BTN16") (pin "2") (pinfunction "2_2") (pintype "passive"))
      (node (ref "BTN17") (pin "2") (pinfunction "2_2") (pintype "passive"))
      (node (ref "P2") (pin "11") (pinfunction "11_11") (pintype "passive"))
    )
    (net (code "55") (name "/SPI_MISO") (class "Default")
      (node (ref "P2") (pin "3") (pinfunction "3_3") (pintype "passive"))
    )
    (net (code "56") (name "/SPI_MOSI") (class "Default")
      (node (ref "IC3") (pin "14") (pinfunction "DS_14") (pintype "passive"))
      (node (ref "P2") (pin "1") (pinfunction "1_1") (pintype "passive"))
    )
    (net (code "57") (name "/SPI_NSS") (class "Default")
      (node (ref "IC3") (pin "12") (pinfunction "STCP_12") (pintype "passive"))
      (node (ref "P4") (pin "12") (pinfunction "12_12") (pintype "passive"))
    )
    (net (code "58") (name "/SPI_SCK") (class "Default")
      (node (ref "IC3") (pin "11") (pinfunction "SHCP_11") (pintype "passive"))
      (node (ref "P4") (pin "2") (pinfunction "2_2") (pintype "passive"))
    )
    (net (code "59") (name "/SWIM") (class "Default")
      (node (ref "MCU1") (pin "26") (pinfunction "PD1(HS)/SWIM_26") (pintype "passive"))
      (node (ref "P7") (pin "2") (pinfunction "2_2") (pintype "passive"))
    )
    (net (code "60") (name "/UART_RX") (class "Default")
      (node (ref "MCU1") (pin "31") (pinfunction "PD6/UART2_RX_31") (pintype "passive"))
      (node (ref "P5") (pin "2") (pinfunction "2_2") (pintype "passive"))
      (node (ref "R6") (pin "2") (pinfunction "2_2") (pintype "passive"))
    )
    (net (code "61") (name "/UART_TX") (class "Default")
      (node (ref "MCU1") (pin "30") (pinfunction "PD5/UART2_TX_30") (pintype "passive"))
      (node (ref "P5") (pin "1") (pinfunction "1_1") (pintype "passive"))
      (node (ref "R7") (pin "2") (pinfunction "2_2") (pintype "passive"))
    )
    (net (code "62") (name "/VCAP") (class "Default")
      (node (ref "C14") (pin "2") (pinfunction "2_2") (pintype "passive"))
      (node (ref "MCU1") (pin "5") (pinfunction "VCAP_5") (pintype "passive"))
    )
    (net (code "63") (name "/XI") (class "Default")
      (node (ref "CR2") (pin "1") (pinfunction "1_1") (pintype "passive"))
      (node (ref "IC2") (pin "7") (pinfunction "XI_7") (pintype "input"))
    )
    (net (code "64") (name "/XO") (class "Default")
      (node (ref "CR2") (pin "3") (pinfunction "3_3") (pintype "passive"))
      (node (ref "IC2") (pin "8") (pinfunction "XO_8") (pintype "output"))
    )
    (net (code "65") (name "/nRST") (class "Default")
      (node (ref "BTN1") (pin "2") (pinfunction "2_2") (pintype "passive"))
      (node (ref "C8") (pin "1") (pinfunction "1_1") (pintype "passive"))
      (node (ref "IC2") (pin "13") (pinfunction "DTR_13") (pintype "bidirectional"))
      (node (ref "MCU1") (pin "1") (pinfunction "NRST_1") (pintype "input"))
      (node (ref "P7") (pin "4") (pinfunction "4_4") (pintype "passive"))
      (node (ref "R1") (pin "1") (pinfunction "1_1") (pintype "passive"))
    )
    (net (code "66") (name "GND") (class "Default")
      (node (ref "B1") (pin "2") (pintype "passive"))
      (node (ref "BTN1") (pin "1") (pinfunction "1_1") (pintype "passive"))
      (node (ref "C1") (pin "2") (pinfunction "2_2") (pintype "passive"))
      (node (ref "C10") (pin "2") (pinfunction "2_2") (pintype "passive"))
      (node (ref "C11") (pin "2") (pinfunction "2_2") (pintype "passive"))
      (node (ref "C12") (pin "2") (pinfunction "2_2") (pintype "passive"))
      (node (ref "C13") (pin "2") (pinfunction "2_2") (pintype "passive"))
      (node (ref "C14") (pin "1") (pinfunction "1_1") (pintype "passive"))
      (node (ref "C15") (pin "1") (pinfunction "1_1") (pintype "passive"))
      (node (ref "C16") (pin "2") (pinfunction "2_2") (pintype "passive"))
      (node (ref "C17") (pin "2") (pinfunction "2_2") (pintype "passive"))
      (node (ref "C18") (pin "2") (pinfunction "2_2") (pintype "passive"))
      (node (ref "C19") (pin "2") (pinfunction "2_2") (pintype "passive"))
      (node (ref "C2") (pin "2") (pinfunction "2_2") (pintype "passive"))
      (node (ref "C3") (pin "2") (pinfunction "2_2") (pintype "passive"))
      (node (ref "C4") (pin "2") (pinfunction "2_2") (pintype "passive"))
      (node (ref "C5") (pin "2") (pinfunction "2_2") (pintype "passive"))
      (node (ref "C6") (pin "2") (pinfunction "2_2") (pintype "passive"))
      (node (ref "C7") (pin "1") (pinfunction "1_1") (pintype "passive"))
      (node (ref "C8") (pin "2") (pinfunction "2_2") (pintype "passive"))
      (node (ref "C9") (pin "2") (pinfunction "2_2") (pintype "passive"))
      (node (ref "CR1") (pin "2") (pinfunction "2_2") (pintype "passive"))
      (node (ref "CR2") (pin "2") (pinfunction "2_2") (pintype "passive"))
      (node (ref "H1") (pin "5") (pinfunction "GND_5") (pintype "passive"))
      (node (ref "IC1") (pin "2") (pinfunction "GND_2") (pintype "power_in"))
      (node (ref "IC2") (pin "1") (pinfunction "GND_1") (pintype "power_in"))
      (node (ref "IC3") (pin "13") (pinfunction "~{OE}_13") (pintype "passive"))
      (node (ref "IC3") (pin "8") (pinfunction "GND_8") (pintype "passive"))
      (node (ref "LED0") (pin "K") (pinfunction "K_K") (pintype "passive"))
      (node (ref "LED1") (pin "K") (pinfunction "K_K") (pintype "passive"))
      (node (ref "LED10") (pin "K") (pinfunction "K_K") (pintype "passive"))
      (node (ref "LED11") (pin "K") (pinfunction "K_K") (pintype "passive"))
      (node (ref "LED12") (pin "K") (pinfunction "K_K") (pintype "passive"))
      (node (ref "LED13") (pin "K") (pinfunction "K_K") (pintype "passive"))
      (node (ref "LED14") (pin "K") (pinfunction "K_K") (pintype "passive"))
      (node (ref "LED15") (pin "K") (pinfunction "K_K") (pintype "passive"))
      (node (ref "LED16") (pin "K") (pinfunction "K_K") (pintype "passive"))
      (node (ref "LED2") (pin "K") (pinfunction "K_K") (pintype "passive"))
      (node (ref "LED3") (pin "K") (pinfunction "K_K") (pintype "passive"))
      (node (ref "LED4") (pin "K") (pinfunction "K_K") (pintype "passive"))
      (node (ref "LED5") (pin "K") (pinfunction "K_K") (pintype "passive"))
      (node (ref "LED6") (pin "K") (pinfunction "K_K") (pintype "passive"))
      (node (ref "LED7") (pin "K") (pinfunction "K_K") (pintype "passive"))
      (node (ref "LED8") (pin "K") (pinfunction "K_K") (pintype "passive"))
      (node (ref "LED9") (pin "K") (pinfunction "K_K") (pintype "passive"))
      (node (ref "MCU1") (pin "10") (pinfunction "VSSA_10") (pintype "power_in"))
      (node (ref "MCU1") (pin "4") (pinfunction "VSS_4") (pintype "power_in"))
      (node (ref "P3") (pin "3") (pinfunction "3_3") (pintype "passive"))
      (node (ref "P3") (pin "4") (pinfunction "4_4") (pintype "passive"))
      (node (ref "P5") (pin "3") (pinfunction "3_3") (pintype "passive"))
      (node (ref "P7") (pin "3") (pinfunction "3_3") (pintype "passive"))
      (node (ref "R3") (pin "1") (pinfunction "1_1") (pintype "passive"))
      (node (ref "U1") (pin "13") (pinfunction "GND_13") (pintype "passive"))
    )
    (net (code "67") (name "GND_USB") (class "Default")
      (node (ref "C16") (pin "1") (pinfunction "1_1") (pintype "passive"))
      (node (ref "C17") (pin "1") (pinfunction "1_1") (pintype "passive"))
      (node (ref "C18") (pin "1") (pinfunction "1_1") (pintype "passive"))
      (node (ref "C19") (pin "1") (pinfunction "1_1") (pintype "passive"))
      (node (ref "H1") (pin "6") (pinfunction "GND_6") (pintype "passive"))
      (node (ref "H1") (pin "7") (pinfunction "GND_7") (pintype "passive"))
      (node (ref "H1") (pin "8") (pinfunction "GND_8") (pintype "passive"))
      (node (ref "H1") (pin "9") (pinfunction "GND_9") (pintype "passive"))
      (node (ref "SC1") (pin "1") (pintype "passive"))
      (node (ref "SC2") (pin "1") (pintype "passive"))
      (node (ref "SC3") (pin "1") (pintype "passive"))
      (node (ref "SC4") (pin "1") (pintype "passive"))
    )
    (net (code "68") (name "Net-(IC1-BYPASS)") (class "Default")
      (node (ref "C1") (pin "1") (pinfunction "1_1") (pintype "passive"))
      (node (ref "IC1") (pin "4") (pinfunction "BYPASS_4") (pintype "passive"))
    )
    (net (code "69") (name "Net-(IC2-RX)") (class "Default")
      (node (ref "IC2") (pin "3") (pinfunction "RX_3") (pintype "input"))
      (node (ref "R7") (pin "1") (pinfunction "1_1") (pintype "passive"))
    )
    (net (code "70") (name "Net-(IC2-TX)") (class "Default")
      (node (ref "IC2") (pin "2") (pinfunction "TX_2") (pintype "output"))
      (node (ref "R6") (pin "1") (pinfunction "1_1") (pintype "passive"))
    )
    (net (code "71") (name "Net-(LED0-PadA)") (class "Default")
      (node (ref "LED0") (pin "A") (pinfunction "A_A") (pintype "passive"))
      (node (ref "R2") (pin "1") (pinfunction "1_1") (pintype "passive"))
    )
    (net (code "72") (name "Net-(LED9-PadA)") (class "Default")
      (node (ref "LED9") (pin "A") (pinfunction "A_A") (pintype "passive"))
      (node (ref "R9") (pin "4") (pinfunction "4_4") (pintype "passive"))
    )
    (net (code "73") (name "Net-(LED10-PadA)") (class "Default")
      (node (ref "LED10") (pin "A") (pinfunction "A_A") (pintype "passive"))
      (node (ref "R9") (pin "3") (pinfunction "3_3") (pintype "passive"))
    )
    (net (code "74") (name "Net-(LED11-PadA)") (class "Default")
      (node (ref "LED11") (pin "A") (pinfunction "A_A") (pintype "passive"))
      (node (ref "R9") (pin "2") (pinfunction "2_2") (pintype "passive"))
    )
    (net (code "75") (name "Net-(LED12-PadA)") (class "Default")
      (node (ref "LED12") (pin "A") (pinfunction "A_A") (pintype "passive"))
      (node (ref "R9") (pin "1") (pinfunction "1_1") (pintype "passive"))
    )
    (net (code "76") (name "Net-(LED13-PadA)") (class "Default")
      (node (ref "LED13") (pin "A") (pinfunction "A_A") (pintype "passive"))
      (node (ref "R11") (pin "1") (pinfunction "1_1") (pintype "passive"))
    )
    (net (code "77") (name "Net-(LED14-PadA)") (class "Default")
      (node (ref "LED14") (pin "A") (pinfunction "A_A") (pintype "passive"))
      (node (ref "R11") (pin "2") (pinfunction "2_2") (pintype "passive"))
    )
    (net (code "78") (name "Net-(LED15-PadA)") (class "Default")
      (node (ref "LED15") (pin "A") (pinfunction "A_A") (pintype "passive"))
      (node (ref "R11") (pin "3") (pinfunction "3_3") (pintype "passive"))
    )
    (net (code "79") (name "Net-(LED16-PadA)") (class "Default")
      (node (ref "LED16") (pin "A") (pinfunction "A_A") (pintype "passive"))
      (node (ref "R11") (pin "4") (pinfunction "4_4") (pintype "passive"))
    )
    (net (code "80") (name "Net-(U1-VBAT)") (class "Default")
      (node (ref "B1") (pin "1") (pintype "passive"))
      (node (ref "U1") (pin "14") (pinfunction "VBAT_14") (pintype "passive"))
    )
    (net (code "81") (name "VDD_3V3") (class "Default")
      (node (ref "C10") (pin "1") (pinfunction "1_1") (pintype "passive"))
      (node (ref "C11") (pin "1") (pinfunction "1_1") (pintype "passive"))
      (node (ref "C12") (pin "1") (pinfunction "1_1") (pintype "passive"))
      (node (ref "C13") (pin "1") (pinfunction "1_1") (pintype "passive"))
      (node (ref "C15") (pin "2") (pinfunction "2_2") (pintype "passive"))
      (node (ref "C3") (pin "1") (pinfunction "1_1") (pintype "passive"))
      (node (ref "C4") (pin "1") (pinfunction "1_1") (pintype "passive"))
      (node (ref "C5") (pin "1") (pinfunction "1_1") (pintype "passive"))
      (node (ref "C6") (pin "1") (pinfunction "1_1") (pintype "passive"))
      (node (ref "C7") (pin "2") (pinfunction "2_2") (pintype "passive"))
      (node (ref "C9") (pin "1") (pinfunction "1_1") (pintype "passive"))
      (node (ref "IC1") (pin "5") (pinfunction "VOUT_5") (pintype "output"))
      (node (ref "IC2") (pin "4") (pinfunction "V3_4") (pintype "power_in"))
      (node (ref "IC3") (pin "10") (pinfunction "~{MR}_10") (pintype "passive"))
      (node (ref "IC3") (pin "16") (pinfunction "VCC_16") (pintype "passive"))
      (node (ref "MCU1") (pin "6") (pinfunction "VDD_6") (pintype "power_in"))
      (node (ref "MCU1") (pin "7") (pinfunction "VDDIO_7") (pintype "power_in"))
      (node (ref "MCU1") (pin "9") (pinfunction "VDDA_9") (pintype "power_in"))
      (node (ref "P3") (pin "2") (pinfunction "2_2") (pintype "passive"))
      (node (ref "P7") (pin "1") (pinfunction "1_1") (pintype "passive"))
      (node (ref "R1") (pin "2") (pinfunction "2_2") (pintype "passive"))
      (node (ref "R2") (pin "2") (pinfunction "2_2") (pintype "passive"))
      (node (ref "R4") (pin "2") (pinfunction "2_2") (pintype "passive"))
      (node (ref "R5") (pin "2") (pinfunction "2_2") (pintype "passive"))
      (node (ref "U1") (pin "2") (pinfunction "VCC_2") (pintype "passive"))
    )
    (net (code "82") (name "VDD_5V") (class "Default")
      (node (ref "C2") (pin "1") (pinfunction "1_1") (pintype "passive"))
      (node (ref "D1") (pin "2") (pinfunction "K_2") (pintype "passive"))
      (node (ref "IC1") (pin "1") (pinfunction "VIN_1") (pintype "input"))
      (node (ref "IC1") (pin "3") (pinfunction "INHIBIT_3") (pintype "input"))
      (node (ref "IC2") (pin "16") (pinfunction "VCC_16") (pintype "power_in"))
      (node (ref "P1") (pin "2") (pinfunction "2_2") (pintype "passive"))
      (node (ref "P3") (pin "1") (pinfunction "1_1") (pintype "passive"))
      (node (ref "TP1") (pin "1") (pintype "passive"))
    )
    (net (code "83") (name "VDD_IN") (class "Default")
      (node (ref "D1") (pin "1") (pinfunction "A_1") (pintype "passive"))
      (node (ref "H1") (pin "1") (pinfunction "VBus_1") (pintype "passive"))
      (node (ref "TP2") (pin "1") (pintype "passive"))
    )
    (net (code "84") (name "unconnected-(H1-NC-Pad4)") (class "Default")
      (node (ref "H1") (pin "4") (pinfunction "NC_4") (pintype "passive+no_connect"))
    )
    (net (code "85") (name "unconnected-(IC2-CTS-Pad9)") (class "Default")
      (node (ref "IC2") (pin "9") (pinfunction "CTS_9") (pintype "bidirectional+no_connect"))
    )
    (net (code "86") (name "unconnected-(IC2-DCD-Pad12)") (class "Default")
      (node (ref "IC2") (pin "12") (pinfunction "DCD_12") (pintype "bidirectional+no_connect"))
    )
    (net (code "87") (name "unconnected-(IC2-DSR-Pad10)") (class "Default")
      (node (ref "IC2") (pin "10") (pinfunction "DSR_10") (pintype "bidirectional+no_connect"))
    )
    (net (code "88") (name "unconnected-(IC2-R232-Pad15)") (class "Default")
      (node (ref "IC2") (pin "15") (pinfunction "R232_15") (pintype "bidirectional+no_connect"))
    )
    (net (code "89") (name "unconnected-(IC2-RI-Pad11)") (class "Default")
      (node (ref "IC2") (pin "11") (pinfunction "RI_11") (pintype "bidirectional+no_connect"))
    )
    (net (code "90") (name "unconnected-(IC2-RTS-Pad14)") (class "Default")
      (node (ref "IC2") (pin "14") (pinfunction "RTS_14") (pintype "bidirectional+no_connect"))
    )
    (net (code "91") (name "unconnected-(IC3-Q7S-Pad9)") (class "Default")
      (node (ref "IC3") (pin "9") (pinfunction "Q7S_9") (pintype "passive+no_connect"))
    )
    (net (code "92") (name "unconnected-(U1-32KHz-Pad1)") (class "Default")
      (node (ref "U1") (pin "1") (pinfunction "32KHz_1") (pintype "passive+no_connect"))
    )
    (net (code "93") (name "unconnected-(U1-INT-Pad3)") (class "Default")
      (node (ref "U1") (pin "3") (pinfunction "INT_3") (pintype "passive+no_connect"))
    )
    (net (code "94") (name "unconnected-(U1-NC-Pad5)") (class "Default")
      (node (ref "U1") (pin "5") (pinfunction "NC_5") (pintype "passive+no_connect"))
    )
    (net (code "95") (name "unconnected-(U1-NC-Pad6)") (class "Default")
      (node (ref "U1") (pin "6") (pinfunction "NC_6") (pintype "passive+no_connect"))
    )
    (net (code "96") (name "unconnected-(U1-NC-Pad7)") (class "Default")
      (node (ref "U1") (pin "7") (pinfunction "NC_7") (pintype "passive+no_connect"))
    )
    (net (code "97") (name "unconnected-(U1-NC-Pad8)") (class "Default")
      (node (ref "U1") (pin "8") (pinfunction "NC_8") (pintype "passive+no_connect"))
    )
    (net (code "98") (name "unconnected-(U1-NC-Pad9)") (class "Default")
      (node (ref "U1") (pin "9") (pinfunction "NC_9") (pintype "passive+no_connect"))
    )
    (net (code "99") (name "unconnected-(U1-NC-Pad10)") (class "Default")
      (node (ref "U1") (pin "10") (pinfunction "NC_10") (pintype "passive+no_connect"))
    )
    (net (code "100") (name "unconnected-(U1-NC-Pad11)") (class "Default")
      (node (ref "U1") (pin "11") (pinfunction "NC_11") (pintype "passive+no_connect"))
    )
    (net (code "101") (name "unconnected-(U1-NC-Pad12)") (class "Default")
      (node (ref "U1") (pin "12") (pinfunction "NC_12") (pintype "passive+no_connect"))
    )
    (net (code "102") (name "unconnected-(U1-RST-Pad4)") (class "Default")
      (node (ref "U1") (pin "4") (pinfunction "RST_4") (pintype "passive+no_connect"))
    )
  )
)
